# SCH_PCB-Paralela_2025-02-01.net
KiCad netlist of a schematic drawn in EasyEDA
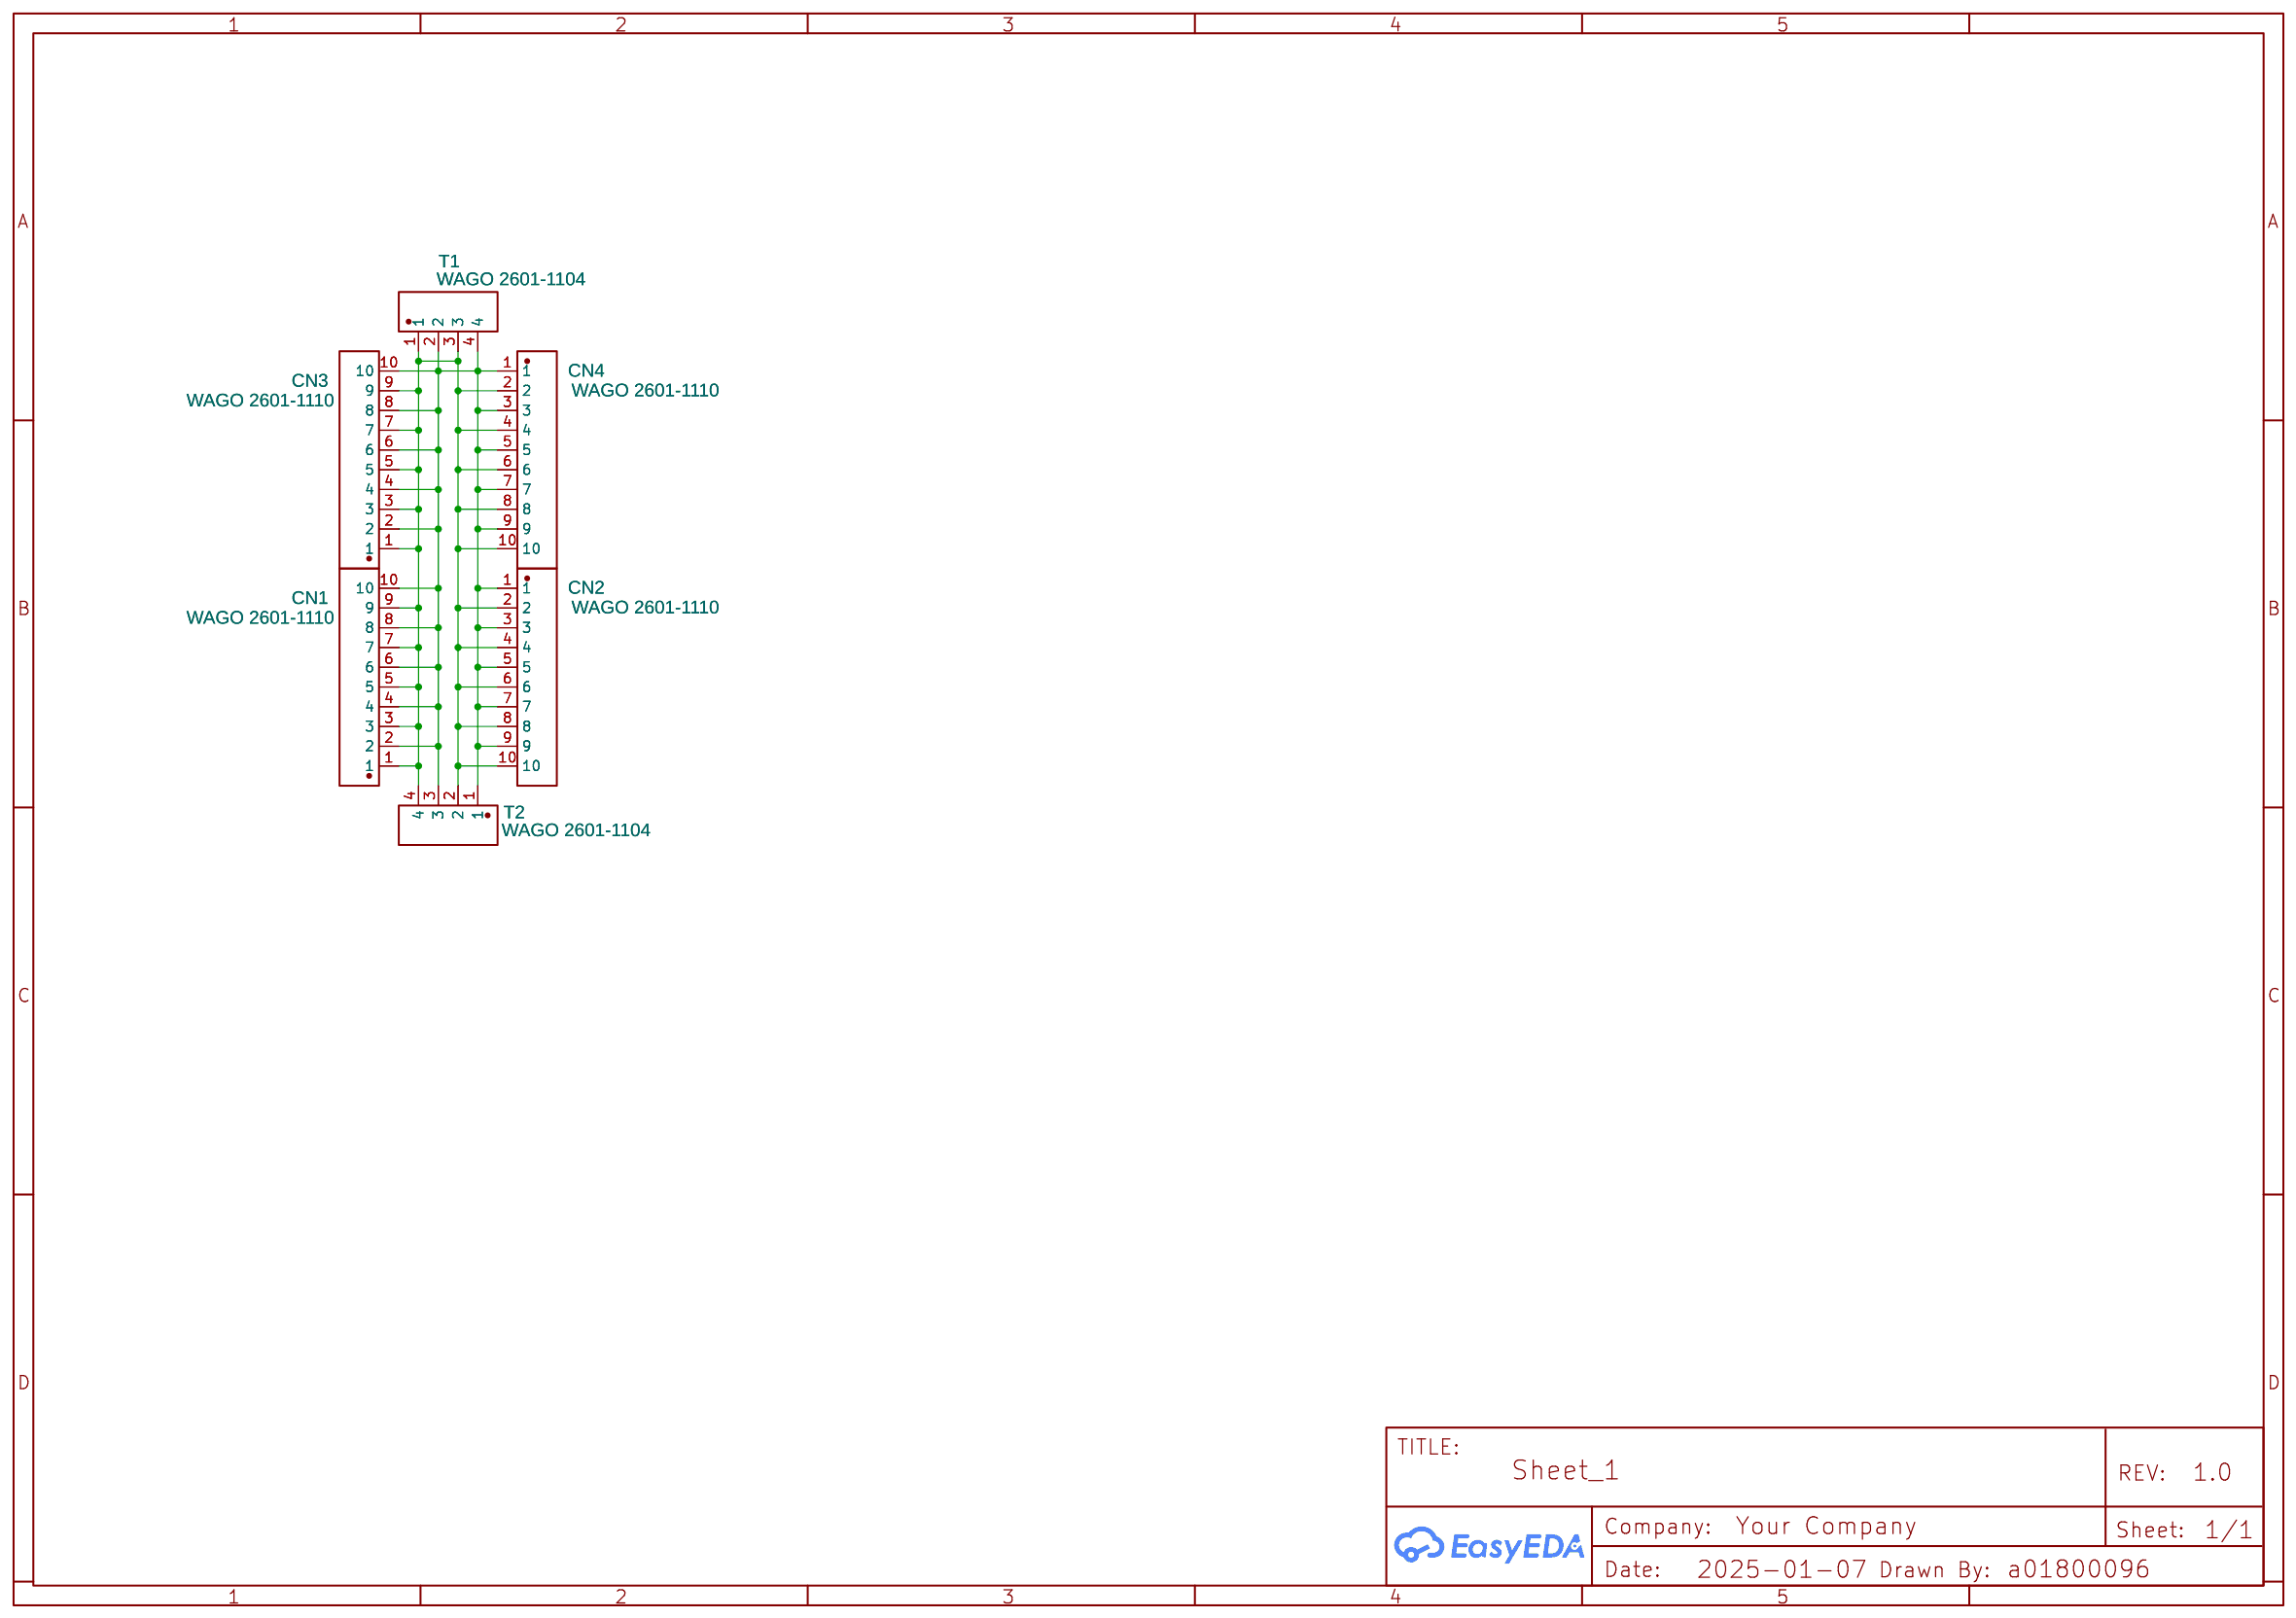
[diagram p0: PCB en Paralelo]
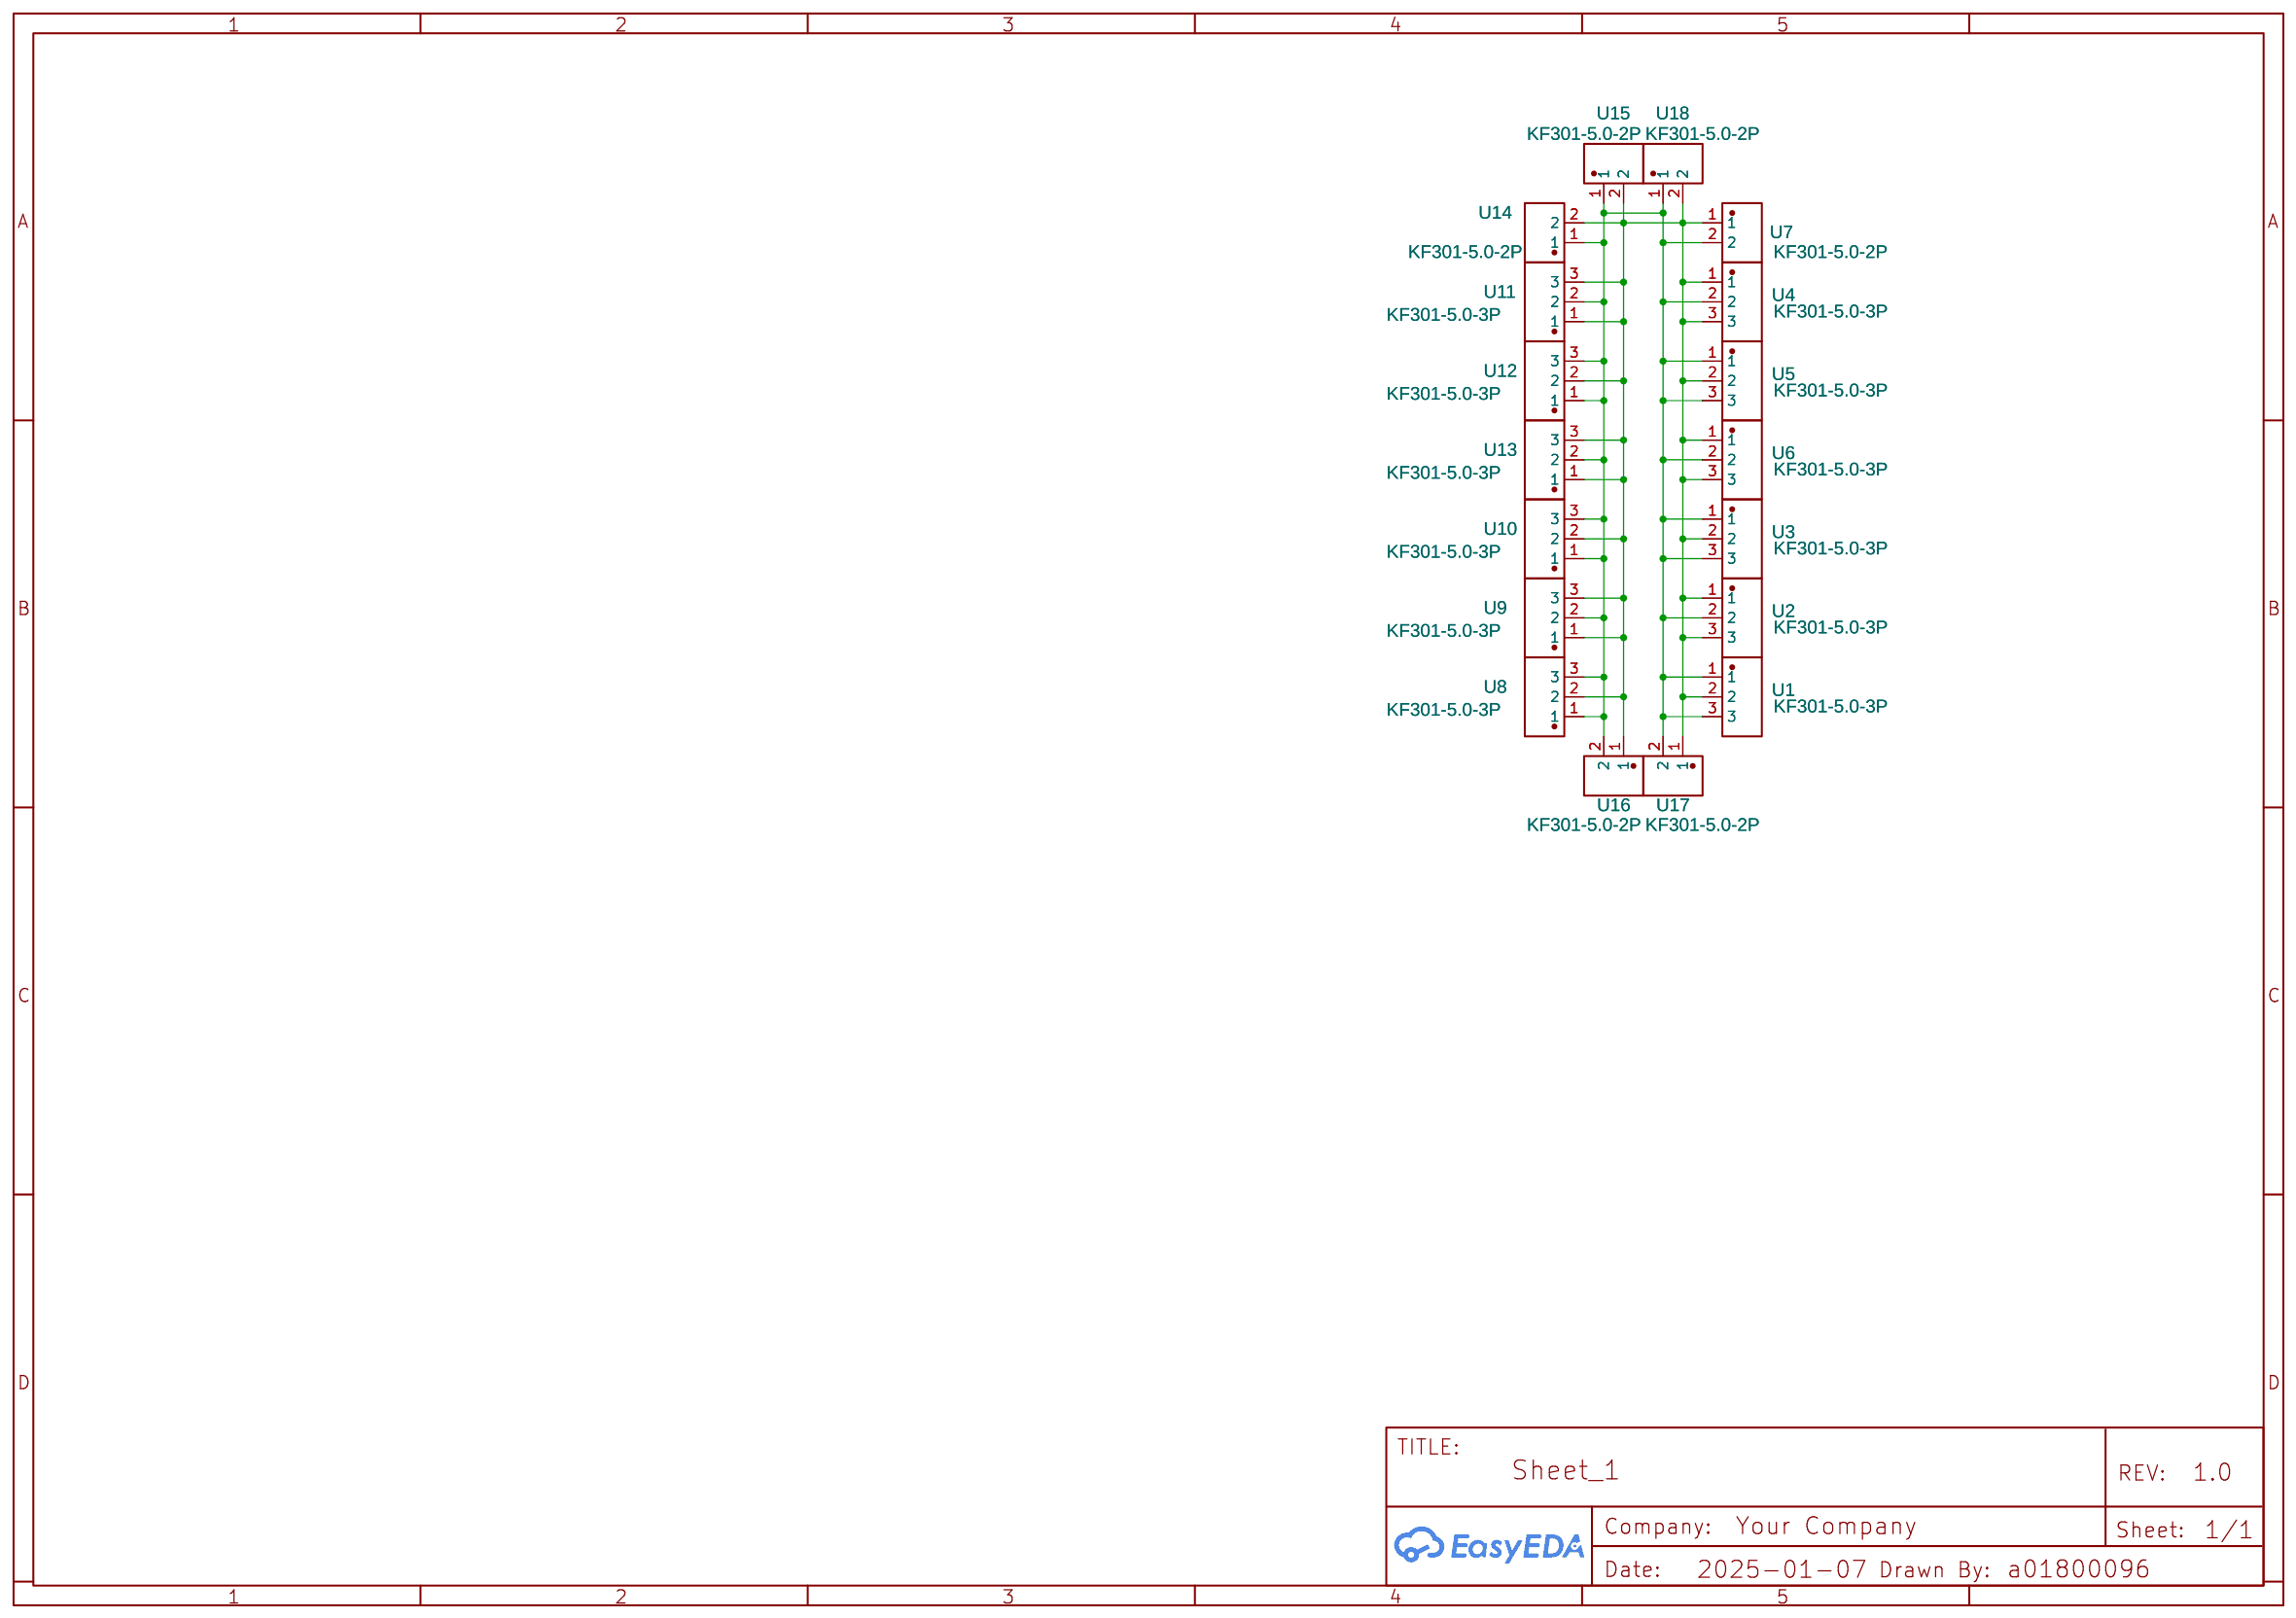
[diagram p1: PCB Final]

(export (version "E")
  (design (tool "Eeschema 10.0.6"))
  (components
    (comp (ref "CN1")
      (value "WAGO 2601-1110")
      (fields (field (name "Manufacturer Part") "CONNECTOR"))
      (libsource (lib "") (part "WAGO 2601-1110_1"))
    )
    (comp (ref "CN2")
      (value "WAGO 2601-1110")
      (fields (field (name "Manufacturer Part") "CONNECTOR"))
      (libsource (lib "") (part "WAGO 2601-1110"))
    )
    (comp (ref "CN3")
      (value "WAGO 2601-1110")
      (fields (field (name "Manufacturer Part") "CONNECTOR"))
      (libsource (lib "") (part "WAGO 2601-1110_1"))
    )
    (comp (ref "CN4")
      (value "WAGO 2601-1110")
      (fields (field (name "Manufacturer Part") "CONNECTOR"))
      (libsource (lib "") (part "WAGO 2601-1110"))
    )
    (comp (ref "T1") (value "WAGO 2601-1104") (libsource (lib "") (part "WAGO 2601-1104_1")))
    (comp (ref "T2") (value "WAGO 2601-1104") (libsource (lib "") (part "WAGO 2601-1104")))
    (comp (ref "U1")
      (value "KF301-5.0-3P")
      (fields (field (name "Manufacturer") "KEFA(科发)"))
      (libsource (lib "") (part "KF301-5.0-3P_1"))
    )
    (comp (ref "U2")
      (value "KF301-5.0-3P")
      (fields (field (name "Manufacturer") "KEFA(科发)"))
      (libsource (lib "") (part "KF301-5.0-3P_1"))
    )
    (comp (ref "U3")
      (value "KF301-5.0-3P")
      (fields (field (name "Manufacturer") "KEFA(科发)"))
      (libsource (lib "") (part "KF301-5.0-3P_1"))
    )
    (comp (ref "U4")
      (value "KF301-5.0-3P")
      (fields (field (name "Manufacturer") "KEFA(科发)"))
      (libsource (lib "") (part "KF301-5.0-3P_1"))
    )
    (comp (ref "U5")
      (value "KF301-5.0-3P")
      (fields (field (name "Manufacturer") "KEFA(科发)"))
      (libsource (lib "") (part "KF301-5.0-3P_1"))
    )
    (comp (ref "U6")
      (value "KF301-5.0-3P")
      (fields (field (name "Manufacturer") "KEFA(科发)"))
      (libsource (lib "") (part "KF301-5.0-3P_1"))
    )
    (comp (ref "U7")
      (value "KF301-5.0-2P")
      (fields (field (name "Manufacturer") "KEFA(科发)"))
      (libsource (lib "") (part "KF301-5.0-2P_1"))
    )
    (comp (ref "U8")
      (value "KF301-5.0-3P")
      (fields (field (name "Manufacturer") "KEFA(科发)"))
      (libsource (lib "") (part "KF301-5.0-3P"))
    )
    (comp (ref "U9")
      (value "KF301-5.0-3P")
      (fields (field (name "Manufacturer") "KEFA(科发)"))
      (libsource (lib "") (part "KF301-5.0-3P"))
    )
    (comp (ref "U10")
      (value "KF301-5.0-3P")
      (fields (field (name "Manufacturer") "KEFA(科发)"))
      (libsource (lib "") (part "KF301-5.0-3P"))
    )
    (comp (ref "U11")
      (value "KF301-5.0-3P")
      (fields (field (name "Manufacturer") "KEFA(科发)"))
      (libsource (lib "") (part "KF301-5.0-3P"))
    )
    (comp (ref "U12")
      (value "KF301-5.0-3P")
      (fields (field (name "Manufacturer") "KEFA(科发)"))
      (libsource (lib "") (part "KF301-5.0-3P"))
    )
    (comp (ref "U13")
      (value "KF301-5.0-3P")
      (fields (field (name "Manufacturer") "KEFA(科发)"))
      (libsource (lib "") (part "KF301-5.0-3P"))
    )
    (comp (ref "U14")
      (value "KF301-5.0-2P")
      (fields (field (name "Manufacturer") "KEFA(科发)"))
      (libsource (lib "") (part "KF301-5.0-2P"))
    )
    (comp (ref "U15")
      (value "KF301-5.0-2P")
      (fields (field (name "Manufacturer") "KEFA(科发)"))
      (libsource (lib "") (part "KF301-5.0-2P_3"))
    )
    (comp (ref "U16")
      (value "KF301-5.0-2P")
      (fields (field (name "Manufacturer") "KEFA(科发)"))
      (libsource (lib "") (part "KF301-5.0-2P_2"))
    )
    (comp (ref "U17")
      (value "KF301-5.0-2P")
      (fields (field (name "Manufacturer") "KEFA(科发)"))
      (libsource (lib "") (part "KF301-5.0-2P_2"))
    )
    (comp (ref "U18")
      (value "KF301-5.0-2P")
      (fields (field (name "Manufacturer") "KEFA(科发)"))
      (libsource (lib "") (part "KF301-5.0-2P_3"))
    )
  )
  (nets
    (net (code "1") (name "Net-(CN1-Pad1)") (class "Default")
      (node (ref "CN1") (pin "1") (pinfunction "1_1") (pintype "unspecified"))
      (node (ref "CN1") (pin "3") (pinfunction "3_3") (pintype "unspecified"))
      (node (ref "CN1") (pin "5") (pinfunction "5_5") (pintype "unspecified"))
      (node (ref "CN1") (pin "7") (pinfunction "7_7") (pintype "unspecified"))
      (node (ref "CN1") (pin "9") (pinfunction "9_9") (pintype "unspecified"))
      (node (ref "CN2") (pin "10") (pinfunction "10_10") (pintype "unspecified"))
      (node (ref "CN2") (pin "2") (pinfunction "2_2") (pintype "unspecified"))
      (node (ref "CN2") (pin "4") (pinfunction "4_4") (pintype "unspecified"))
      (node (ref "CN2") (pin "6") (pinfunction "6_6") (pintype "unspecified"))
      (node (ref "CN2") (pin "8") (pinfunction "8_8") (pintype "unspecified"))
      (node (ref "CN3") (pin "1") (pinfunction "1_1") (pintype "unspecified"))
      (node (ref "CN3") (pin "3") (pinfunction "3_3") (pintype "unspecified"))
      (node (ref "CN3") (pin "5") (pinfunction "5_5") (pintype "unspecified"))
      (node (ref "CN3") (pin "7") (pinfunction "7_7") (pintype "unspecified"))
      (node (ref "CN3") (pin "9") (pinfunction "9_9") (pintype "unspecified"))
      (node (ref "CN4") (pin "10") (pinfunction "10_10") (pintype "unspecified"))
      (node (ref "CN4") (pin "2") (pinfunction "2_2") (pintype "unspecified"))
      (node (ref "CN4") (pin "4") (pinfunction "4_4") (pintype "unspecified"))
      (node (ref "CN4") (pin "6") (pinfunction "6_6") (pintype "unspecified"))
      (node (ref "CN4") (pin "8") (pinfunction "8_8") (pintype "unspecified"))
      (node (ref "T1") (pin "1") (pinfunction "1_1") (pintype "unspecified"))
      (node (ref "T1") (pin "3") (pinfunction "3_3") (pintype "unspecified"))
      (node (ref "T2") (pin "2") (pinfunction "2_2") (pintype "unspecified"))
      (node (ref "T2") (pin "4") (pinfunction "4_4") (pintype "unspecified"))
    )
    (net (code "2") (name "Net-(CN1-Pad10)") (class "Default")
      (node (ref "CN1") (pin "10") (pinfunction "10_10") (pintype "unspecified"))
      (node (ref "CN1") (pin "2") (pinfunction "2_2") (pintype "unspecified"))
      (node (ref "CN1") (pin "4") (pinfunction "4_4") (pintype "unspecified"))
      (node (ref "CN1") (pin "6") (pinfunction "6_6") (pintype "unspecified"))
      (node (ref "CN1") (pin "8") (pinfunction "8_8") (pintype "unspecified"))
      (node (ref "CN2") (pin "1") (pinfunction "1_1") (pintype "unspecified"))
      (node (ref "CN2") (pin "3") (pinfunction "3_3") (pintype "unspecified"))
      (node (ref "CN2") (pin "5") (pinfunction "5_5") (pintype "unspecified"))
      (node (ref "CN2") (pin "7") (pinfunction "7_7") (pintype "unspecified"))
      (node (ref "CN2") (pin "9") (pinfunction "9_9") (pintype "unspecified"))
      (node (ref "CN3") (pin "10") (pinfunction "10_10") (pintype "unspecified"))
      (node (ref "CN3") (pin "2") (pinfunction "2_2") (pintype "unspecified"))
      (node (ref "CN3") (pin "4") (pinfunction "4_4") (pintype "unspecified"))
      (node (ref "CN3") (pin "6") (pinfunction "6_6") (pintype "unspecified"))
      (node (ref "CN3") (pin "8") (pinfunction "8_8") (pintype "unspecified"))
      (node (ref "CN4") (pin "1") (pinfunction "1_1") (pintype "unspecified"))
      (node (ref "CN4") (pin "3") (pinfunction "3_3") (pintype "unspecified"))
      (node (ref "CN4") (pin "5") (pinfunction "5_5") (pintype "unspecified"))
      (node (ref "CN4") (pin "7") (pinfunction "7_7") (pintype "unspecified"))
      (node (ref "CN4") (pin "9") (pinfunction "9_9") (pintype "unspecified"))
      (node (ref "T1") (pin "2") (pinfunction "2_2") (pintype "unspecified"))
      (node (ref "T1") (pin "4") (pinfunction "4_4") (pintype "unspecified"))
      (node (ref "T2") (pin "1") (pinfunction "1_1") (pintype "unspecified"))
      (node (ref "T2") (pin "3") (pinfunction "3_3") (pintype "unspecified"))
    )
    (net (code "3") (name "Net-(U1-Pad1)") (class "Default")
      (node (ref "U1") (pin "1") (pinfunction "1_1") (pintype "unspecified"))
      (node (ref "U1") (pin "3") (pinfunction "3_3") (pintype "unspecified"))
      (node (ref "U10") (pin "1") (pinfunction "1_1") (pintype "unspecified"))
      (node (ref "U10") (pin "3") (pinfunction "3_3") (pintype "unspecified"))
      (node (ref "U11") (pin "2") (pinfunction "2_2") (pintype "unspecified"))
      (node (ref "U12") (pin "1") (pinfunction "1_1") (pintype "unspecified"))
      (node (ref "U12") (pin "3") (pinfunction "3_3") (pintype "unspecified"))
      (node (ref "U13") (pin "2") (pinfunction "2_2") (pintype "unspecified"))
      (node (ref "U14") (pin "1") (pinfunction "1_1") (pintype "unspecified"))
      (node (ref "U15") (pin "1") (pinfunction "1_1") (pintype "unspecified"))
      (node (ref "U16") (pin "2") (pinfunction "2_2") (pintype "unspecified"))
      (node (ref "U17") (pin "2") (pinfunction "2_2") (pintype "unspecified"))
      (node (ref "U18") (pin "1") (pinfunction "1_1") (pintype "unspecified"))
      (node (ref "U2") (pin "2") (pinfunction "2_2") (pintype "unspecified"))
      (node (ref "U3") (pin "1") (pinfunction "1_1") (pintype "unspecified"))
      (node (ref "U3") (pin "3") (pinfunction "3_3") (pintype "unspecified"))
      (node (ref "U4") (pin "2") (pinfunction "2_2") (pintype "unspecified"))
      (node (ref "U5") (pin "1") (pinfunction "1_1") (pintype "unspecified"))
      (node (ref "U5") (pin "3") (pinfunction "3_3") (pintype "unspecified"))
      (node (ref "U6") (pin "2") (pinfunction "2_2") (pintype "unspecified"))
      (node (ref "U7") (pin "2") (pinfunction "2_2") (pintype "unspecified"))
      (node (ref "U8") (pin "1") (pinfunction "1_1") (pintype "unspecified"))
      (node (ref "U8") (pin "3") (pinfunction "3_3") (pintype "unspecified"))
      (node (ref "U9") (pin "2") (pinfunction "2_2") (pintype "unspecified"))
    )
    (net (code "4") (name "Net-(U1-Pad2)") (class "Default")
      (node (ref "U1") (pin "2") (pinfunction "2_2") (pintype "unspecified"))
      (node (ref "U10") (pin "2") (pinfunction "2_2") (pintype "unspecified"))
      (node (ref "U11") (pin "1") (pinfunction "1_1") (pintype "unspecified"))
      (node (ref "U11") (pin "3") (pinfunction "3_3") (pintype "unspecified"))
      (node (ref "U12") (pin "2") (pinfunction "2_2") (pintype "unspecified"))
      (node (ref "U13") (pin "1") (pinfunction "1_1") (pintype "unspecified"))
      (node (ref "U13") (pin "3") (pinfunction "3_3") (pintype "unspecified"))
      (node (ref "U14") (pin "2") (pinfunction "2_2") (pintype "unspecified"))
      (node (ref "U15") (pin "2") (pinfunction "2_2") (pintype "unspecified"))
      (node (ref "U16") (pin "1") (pinfunction "1_1") (pintype "unspecified"))
      (node (ref "U17") (pin "1") (pinfunction "1_1") (pintype "unspecified"))
      (node (ref "U18") (pin "2") (pinfunction "2_2") (pintype "unspecified"))
      (node (ref "U2") (pin "1") (pinfunction "1_1") (pintype "unspecified"))
      (node (ref "U2") (pin "3") (pinfunction "3_3") (pintype "unspecified"))
      (node (ref "U3") (pin "2") (pinfunction "2_2") (pintype "unspecified"))
      (node (ref "U4") (pin "1") (pinfunction "1_1") (pintype "unspecified"))
      (node (ref "U4") (pin "3") (pinfunction "3_3") (pintype "unspecified"))
      (node (ref "U5") (pin "2") (pinfunction "2_2") (pintype "unspecified"))
      (node (ref "U6") (pin "1") (pinfunction "1_1") (pintype "unspecified"))
      (node (ref "U6") (pin "3") (pinfunction "3_3") (pintype "unspecified"))
      (node (ref "U7") (pin "1") (pinfunction "1_1") (pintype "unspecified"))
      (node (ref "U8") (pin "2") (pinfunction "2_2") (pintype "unspecified"))
      (node (ref "U9") (pin "1") (pinfunction "1_1") (pintype "unspecified"))
      (node (ref "U9") (pin "3") (pinfunction "3_3") (pintype "unspecified"))
    )
  )
)
